# MCU.net
KiCad netlist of a schematic drawn in Altium Designer
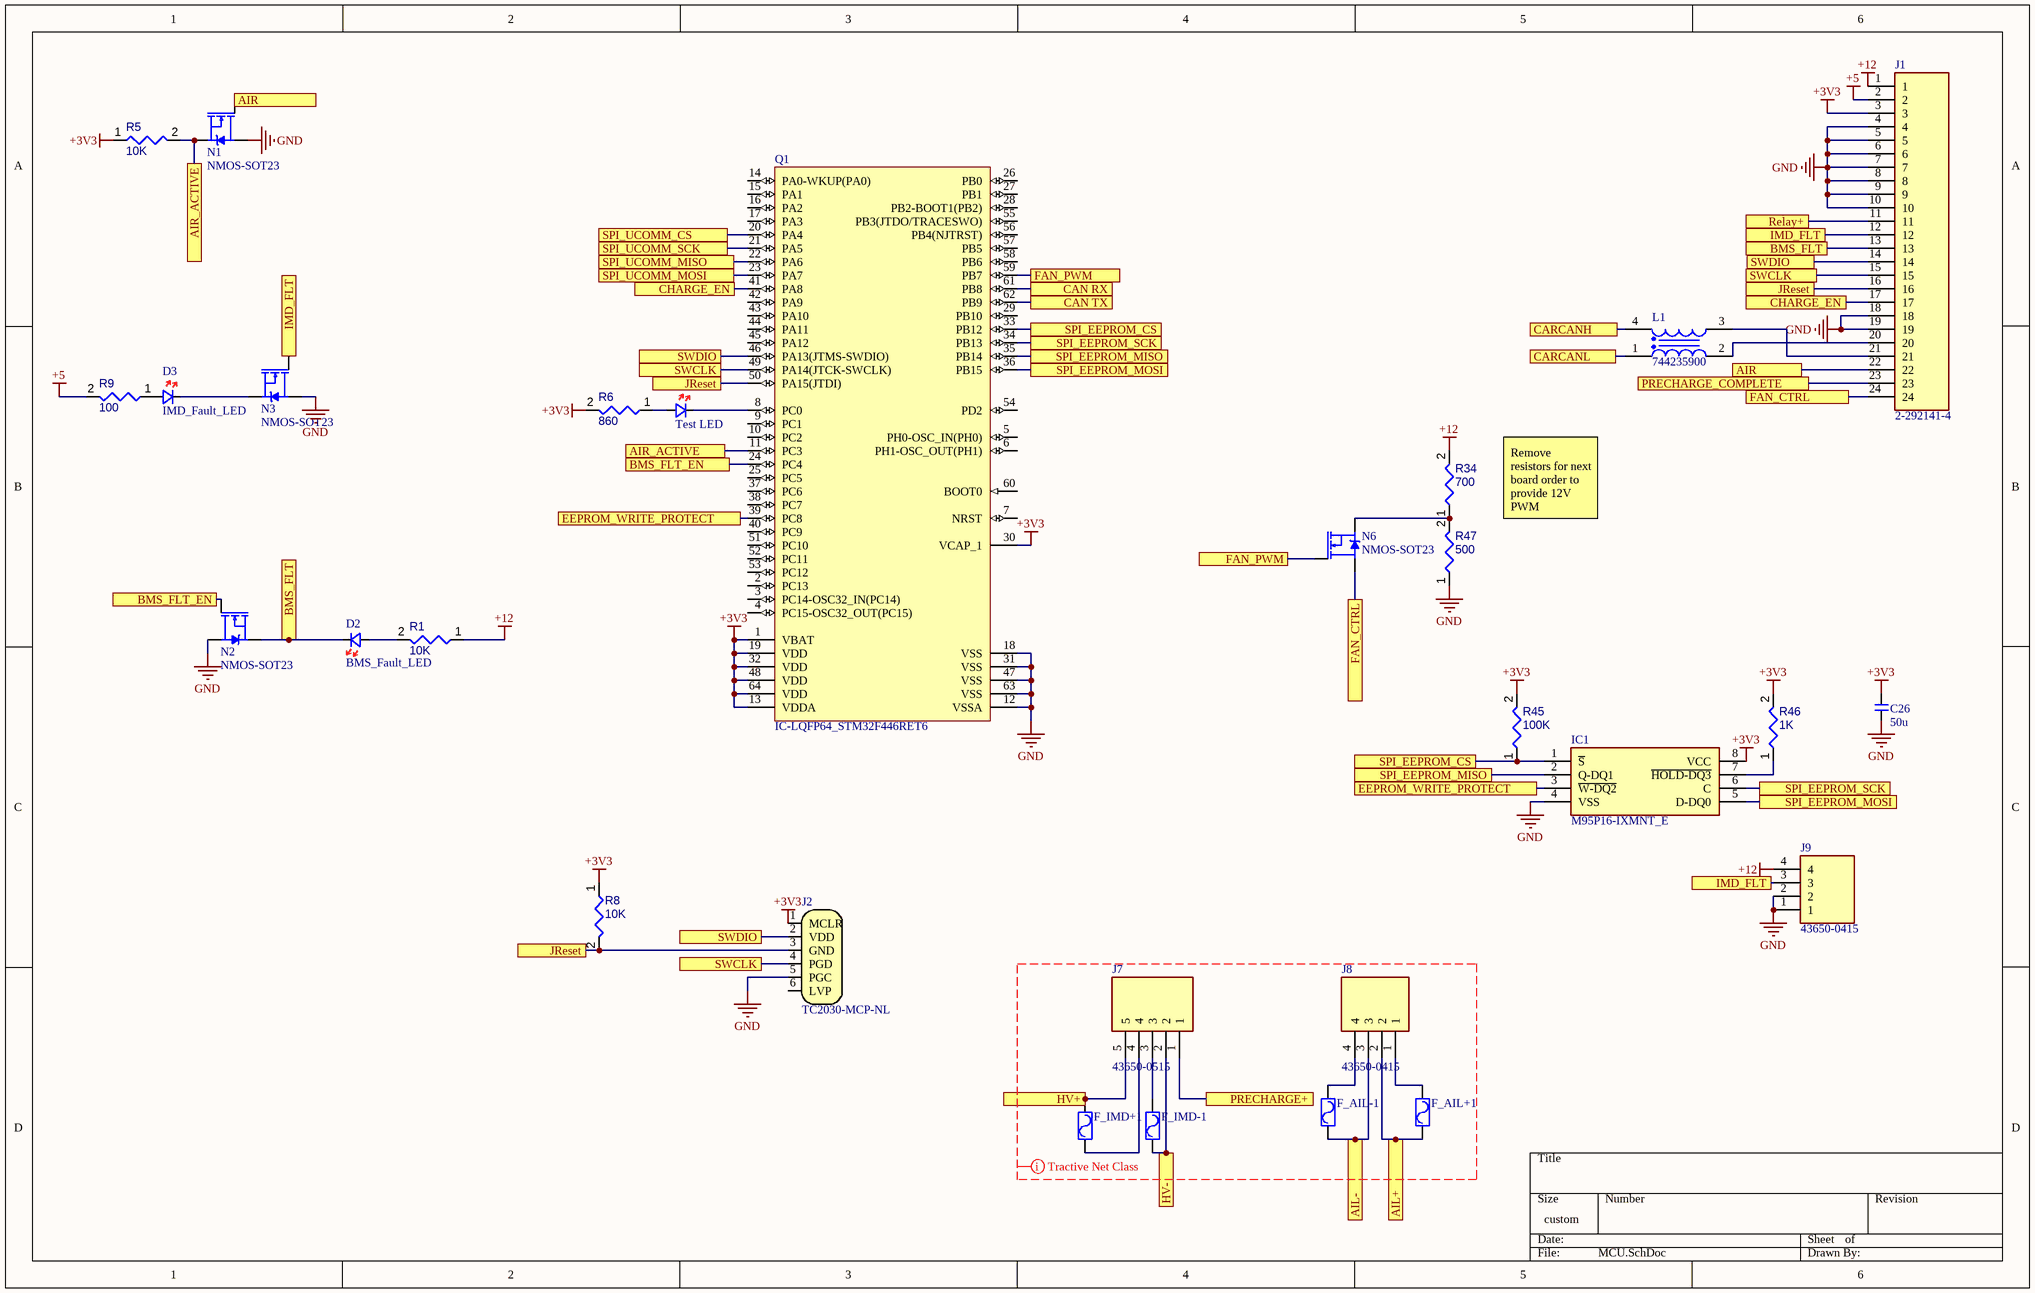
[diagram p0: MCU.SchDoc]

(export (version "E")
  (design (tool "Eeschema 10.0.6"))
  (components
    (comp (ref "C26")
      (value "50u")
      (footprint "CAP-0603")
      (fields (field (name "SOURCE") "ife19_Elec_Library.SchLib"))
      (libsource (lib "Illini Formula Electric") (part "CAP-0603"))
    )
    (comp (ref "D1")
      (value "Test LED")
      (footprint "LEDRED-0603")
      (fields (field (name "SOURCE") "ife19_Elec_Library.SchLib"))
      (libsource (lib "Illini Formula Electric") (part "LED_XZFBB45S"))
    )
    (comp (ref "D2")
      (value "BMS_Fault_LED")
      (footprint "LEDRED-0603")
      (fields (field (name "SOURCE") "ife19_Elec_Library.SchLib"))
      (libsource (lib "Illini Formula Electric") (part "LED_XZFBB45S"))
    )
    (comp (ref "D3")
      (value "IMD_Fault_LED")
      (footprint "LEDRED-0603")
      (fields (field (name "SOURCE") "ife19_Elec_Library.SchLib"))
      (libsource (lib "Illini Formula Electric") (part "LED_XZFBB45S"))
    )
    (comp (ref "F_AIL+1")
      (value "~")
      (footprint "FUSE_885")
      (fields (field (name "SOURCE") "ife19_Elec_Library.SchLib"))
      (libsource (lib "Illini Formula Electric") (part "FUSE-354101"))
    )
    (comp (ref "F_AIL-1")
      (value "~")
      (footprint "FUSE_885")
      (fields (field (name "SOURCE") "ife19_Elec_Library.SchLib"))
      (libsource (lib "Illini Formula Electric") (part "FUSE-354101"))
    )
    (comp (ref "F_IMD+1")
      (value "~")
      (footprint "FUSE_885")
      (fields (field (name "SOURCE") "ife19_Elec_Library.SchLib"))
      (libsource (lib "Illini Formula Electric") (part "FUSE-354101"))
    )
    (comp (ref "F_IMD-1")
      (value "~")
      (footprint "FUSE_885")
      (fields (field (name "SOURCE") "ife19_Elec_Library.SchLib"))
      (libsource (lib "Illini Formula Electric") (part "FUSE-354101"))
    )
    (comp (ref "IC1")
      (value "M95P16-IXMNT_E")
      (footprint "SamacSys:SOIC127P600X175-8N")
      (description "Integrated Circuit")
      (fields (field (name "MANUFACTURER_PART_NUMBER") "M95P16-IXMNT/E"))
      (libsource (lib "*") (part "M95P16-IXMNT_E"))
    )
    (comp (ref "J1")
      (value "2-292141-4")
      (footprint "TE_2-292141-4")
      (description "CT DOUBLE ROW ASSY V 24P W/BOS")
      (fields (field (name "MF") "TE Connectivity"))
      (libsource (lib "Illini Formula Electric") (part "2-292141-4"))
    )
    (comp (ref "J2")
      (value "TC2030-MCP-NL")
      (footprint "TC2030-MCP-NL")
      (description "Conector par ICD")
      (fields (field (name "SOURCE") "Image Pasted at 2021-10-31 17-08.SchLib"))
      (libsource (lib "Illini Formula Electric") (part "TC2030-MCP-NL"))
    )
    (comp (ref "J7")
      (value "43650-0515")
      (footprint "SamacSys:43650-05YY_151617")
      (description "Connector")
      (fields (field (name "MOUSER PART NUMBER") "538-43650-0515"))
      (libsource (lib "*") (part "43650-0515"))
    )
    (comp (ref "J8")
      (value "43650-0415")
      (footprint "SamacSys:43650-04YY_151617")
      (description "Connector")
      (fields (field (name "MOUSER PART NUMBER") "538-43650-0415"))
      (libsource (lib "*") (part "43650-0415"))
    )
    (comp (ref "J9")
      (value "43650-0415")
      (footprint "SamacSys:43650-04YY_151617")
      (description "Connector")
      (fields (field (name "MOUSER PART NUMBER") "538-43650-0415"))
      (libsource (lib "") (part "43650-0415_1"))
    )
    (comp (ref "L1")
      (value "744235900")
      (footprint "WE-CNSW_1812")
      (fields (field (name "TOLERANCE") "25%"))
      (libsource (lib "Altium Content Vault") (part "WE-CNSW"))
    )
    (comp (ref "N1")
      (value "NMOS-SOT23")
      (footprint "SOT23")
      (fields (field (name "SOURCE") "ife19_Elec_Library.SchLib"))
      (libsource (lib "Illini Formula Electric") (part "NMOS-SOT23"))
    )
    (comp (ref "N2")
      (value "NMOS-SOT23")
      (footprint "SOT23")
      (fields (field (name "SOURCE") "ife19_Elec_Library.SchLib"))
      (libsource (lib "Illini Formula Electric") (part "NMOS-SOT23"))
    )
    (comp (ref "N3")
      (value "NMOS-SOT23")
      (footprint "SOT23")
      (fields (field (name "SOURCE") "ife19_Elec_Library.SchLib"))
      (libsource (lib "Illini Formula Electric") (part "NMOS-SOT23"))
    )
    (comp (ref "N6")
      (value "NMOS-SOT23")
      (footprint "SOT23")
      (fields (field (name "SOURCE") "ife19_Elec_Library.SchLib"))
      (libsource (lib "Illini Formula Electric") (part "NMOS-SOT23"))
    )
    (comp (ref "Q1")
      (value "IC-LQFP64_STM32F446RET6")
      (footprint "TSQFP50P1200X1200X160-64N")
      (description "IC MCU 32BIT 512KB FLASH 64LQFP")
      (fields
        (field (name "MANUFACTURER PART NUMBER") "STM32F446RET6")
        (field (name "MANUFACTURER") "STMicroelectronics")
        (field (name "SOURCE") "ife19_Elec_Library.SchLib")
      )
      (libsource (lib "Illini Formula Electric") (part "IC-LQFP64_STM32F446RET6"))
    )
    (comp (ref "R1")
      (value "10K")
      (footprint "RESC0805(2012)_L")
      (description "Chip Resistor, 43,2 kOhms, +/-1 %, 63 mW, -55 to 155 degC, 0402")
      (fields (field (name "AVAILABLE PREVIEW IMAGES") "2D"))
      (libsource (lib "Illini Formula Electric") (part "Symbol"))
    )
    (comp (ref "R5")
      (value "10K")
      (footprint "RESC0805(2012)_L")
      (description "Chip Resistor, 43,2 kOhms, +/-1 %, 63 mW, -55 to 155 degC, 0402")
      (fields (field (name "AVAILABLE PREVIEW IMAGES") "2D"))
      (libsource (lib "Illini Formula Electric") (part "Symbol"))
    )
    (comp (ref "R6")
      (value "860")
      (footprint "RESC0805(2012)_L")
      (description "Chip Resistor, 43,2 kOhms, +/-1 %, 63 mW, -55 to 155 degC, 0402")
      (fields (field (name "AVAILABLE PREVIEW IMAGES") "2D"))
      (libsource (lib "Illini Formula Electric") (part "Symbol"))
    )
    (comp (ref "R8")
      (value "10K")
      (footprint "RESC0805(2012)_L")
      (description "Chip Resistor, 43,2 kOhms, +/-1 %, 63 mW, -55 to 155 degC, 0402")
      (fields (field (name "AVAILABLE PREVIEW IMAGES") "2D"))
      (libsource (lib "Illini Formula Electric") (part "Symbol"))
    )
    (comp (ref "R9")
      (value "100")
      (footprint "RESC0805(2012)_L")
      (description "Chip Resistor, 43,2 kOhms, +/-1 %, 63 mW, -55 to 155 degC, 0402")
      (fields (field (name "AVAILABLE PREVIEW IMAGES") "2D"))
      (libsource (lib "Illini Formula Electric") (part "Symbol"))
    )
    (comp (ref "R34")
      (value "700")
      (footprint "RESC0805(2012)_L")
      (description "Chip Resistor, 43,2 kOhms, +/-1 %, 63 mW, -55 to 155 degC, 0402")
      (fields (field (name "AVAILABLE PREVIEW IMAGES") "2D"))
      (libsource (lib "Illini Formula Electric") (part "Symbol"))
    )
    (comp (ref "R45")
      (value "100K")
      (footprint "RESC0805(2012)_L")
      (description "Chip Resistor, 43,2 kOhms, +/-1 %, 63 mW, -55 to 155 degC, 0402")
      (fields (field (name "AVAILABLE PREVIEW IMAGES") "2D"))
      (libsource (lib "Illini Formula Electric") (part "Symbol"))
    )
    (comp (ref "R46")
      (value "1K")
      (footprint "RESC0805(2012)_L")
      (description "Chip Resistor, 43,2 kOhms, +/-1 %, 63 mW, -55 to 155 degC, 0402")
      (fields (field (name "AVAILABLE PREVIEW IMAGES") "2D"))
      (libsource (lib "Illini Formula Electric") (part "Symbol"))
    )
    (comp (ref "R47")
      (value "500")
      (footprint "RESC0805(2012)_L")
      (description "Chip Resistor, 43,2 kOhms, +/-1 %, 63 mW, -55 to 155 degC, 0402")
      (fields (field (name "AVAILABLE PREVIEW IMAGES") "2D"))
      (libsource (lib "Illini Formula Electric") (part "Symbol"))
    )
  )
  (nets
    (net (code "1") (name "+3V3") (class "Default")
      (node (ref "C26") (pin "1") (pinfunction "1_1") (pintype "passive"))
      (node (ref "IC1") (pin "8") (pinfunction "VCC_8") (pintype "passive"))
      (node (ref "J1") (pin "3") (pinfunction "3_3") (pintype "passive"))
      (node (ref "J2") (pin "1") (pinfunction "MCLR_1") (pintype "passive"))
      (node (ref "Q1") (pin "1") (pinfunction "VBAT_1") (pintype "power_in"))
      (node (ref "Q1") (pin "13") (pinfunction "VDDA_13") (pintype "power_in"))
      (node (ref "Q1") (pin "19") (pinfunction "VDD_19") (pintype "power_in"))
      (node (ref "Q1") (pin "30") (pinfunction "VCAP_1_30") (pintype "passive"))
      (node (ref "Q1") (pin "32") (pinfunction "VDD_32") (pintype "power_in"))
      (node (ref "Q1") (pin "48") (pinfunction "VDD_48") (pintype "power_in"))
      (node (ref "Q1") (pin "64") (pinfunction "VDD_64") (pintype "power_in"))
      (node (ref "R45") (pin "2") (pinfunction "2_2") (pintype "passive"))
      (node (ref "R46") (pin "2") (pinfunction "2_2") (pintype "passive"))
      (node (ref "R5") (pin "1") (pinfunction "1_1") (pintype "passive"))
      (node (ref "R6") (pin "2") (pinfunction "2_2") (pintype "passive"))
      (node (ref "R8") (pin "1") (pinfunction "1_1") (pintype "passive"))
    )
    (net (code "2") (name "+5") (class "Default")
      (node (ref "J1") (pin "2") (pinfunction "2_2") (pintype "passive"))
      (node (ref "R9") (pin "2") (pinfunction "2_2") (pintype "passive"))
    )
    (net (code "3") (name "+12") (class "Default")
      (node (ref "J1") (pin "1") (pinfunction "1_1") (pintype "passive"))
      (node (ref "J9") (pin "4") (pinfunction "4_4") (pintype "passive"))
      (node (ref "R1") (pin "1") (pinfunction "1_1") (pintype "passive"))
      (node (ref "R34") (pin "2") (pinfunction "2_2") (pintype "passive"))
    )
    (net (code "4") (name "/AIL+") (class "Default")
      (node (ref "F_AIL+1") (pin "2") (pinfunction "2_2") (pintype "passive"))
      (node (ref "J8") (pin "2") (pinfunction "2_2") (pintype "passive"))
    )
    (net (code "5") (name "/AIL-") (class "Default")
      (node (ref "F_AIL-1") (pin "2") (pinfunction "2_2") (pintype "passive"))
      (node (ref "J8") (pin "3") (pinfunction "3_3") (pintype "passive"))
    )
    (net (code "6") (name "/AIR") (class "Default")
      (node (ref "J1") (pin "22") (pinfunction "22_22") (pintype "passive"))
      (node (ref "N1") (pin "1") (pinfunction "G_1") (pintype "passive"))
    )
    (net (code "7") (name "/AIR_ACTIVE") (class "Default")
      (node (ref "N1") (pin "3") (pinfunction "D_3") (pintype "passive"))
      (node (ref "Q1") (pin "11") (pinfunction "PC3_11") (pintype "bidirectional"))
      (node (ref "R5") (pin "2") (pinfunction "2_2") (pintype "passive"))
    )
    (net (code "8") (name "/BMS_FLT") (class "Default")
      (node (ref "D2") (pin "K") (pinfunction "K_K") (pintype "passive"))
      (node (ref "J1") (pin "13") (pinfunction "13_13") (pintype "passive"))
      (node (ref "N2") (pin "3") (pinfunction "D_3") (pintype "passive"))
    )
    (net (code "9") (name "/BMS_FLT_EN") (class "Default")
      (node (ref "N2") (pin "1") (pinfunction "G_1") (pintype "passive"))
      (node (ref "Q1") (pin "24") (pinfunction "PC4_24") (pintype "bidirectional"))
    )
    (net (code "10") (name "/CAN RX") (class "Default")
      (node (ref "Q1") (pin "61") (pinfunction "PB8_61") (pintype "bidirectional"))
    )
    (net (code "11") (name "/CAN TX") (class "Default")
      (node (ref "Q1") (pin "62") (pinfunction "PB9_62") (pintype "bidirectional"))
    )
    (net (code "12") (name "/CARCANH") (class "Default")
      (node (ref "L1") (pin "4") (pinfunction "4_4") (pintype "passive"))
    )
    (net (code "13") (name "/CARCANL") (class "Default")
      (node (ref "L1") (pin "1") (pinfunction "1_1") (pintype "passive"))
    )
    (net (code "14") (name "/CHARGE_EN") (class "Default")
      (node (ref "J1") (pin "17") (pinfunction "17_17") (pintype "passive"))
      (node (ref "Q1") (pin "41") (pinfunction "PA8_41") (pintype "bidirectional"))
    )
    (net (code "15") (name "/EEPROM_WRITE_PROTECT") (class "Default")
      (node (ref "IC1") (pin "3") (pinfunction "~{W-DQ2}_3") (pintype "passive"))
      (node (ref "Q1") (pin "39") (pinfunction "PC8_39") (pintype "bidirectional"))
    )
    (net (code "16") (name "/FAN_CTRL") (class "Default")
      (node (ref "J1") (pin "24") (pinfunction "24_24") (pintype "passive"))
      (node (ref "N6") (pin "2") (pinfunction "S_2") (pintype "passive"))
    )
    (net (code "17") (name "/FAN_PWM") (class "Default")
      (node (ref "N6") (pin "1") (pinfunction "G_1") (pintype "passive"))
      (node (ref "Q1") (pin "59") (pinfunction "PB7_59") (pintype "bidirectional"))
    )
    (net (code "18") (name "/HV+") (class "Default")
      (node (ref "F_IMD+1") (pin "1") (pinfunction "1_1") (pintype "passive"))
      (node (ref "J7") (pin "5") (pinfunction "5_5") (pintype "passive"))
    )
    (net (code "19") (name "/HV-") (class "Default")
      (node (ref "F_IMD-1") (pin "2") (pinfunction "2_2") (pintype "passive"))
      (node (ref "J7") (pin "2") (pinfunction "2_2") (pintype "passive"))
    )
    (net (code "20") (name "/IMD_FLT") (class "Default")
      (node (ref "J1") (pin "12") (pinfunction "12_12") (pintype "passive"))
      (node (ref "J9") (pin "3") (pinfunction "3_3") (pintype "passive"))
      (node (ref "N3") (pin "1") (pinfunction "G_1") (pintype "passive"))
    )
    (net (code "21") (name "/JReset") (class "Default")
      (node (ref "J1") (pin "16") (pinfunction "16_16") (pintype "passive"))
      (node (ref "J2") (pin "3") (pinfunction "GND_3") (pintype "passive"))
      (node (ref "Q1") (pin "50") (pinfunction "PA15(JTDI)_50") (pintype "bidirectional"))
      (node (ref "R8") (pin "2") (pinfunction "2_2") (pintype "passive"))
    )
    (net (code "22") (name "/PRECHARGE+") (class "Default")
      (node (ref "J7") (pin "1") (pinfunction "1_1") (pintype "passive"))
    )
    (net (code "23") (name "/PRECHARGE_COMPLETE") (class "Default")
      (node (ref "J1") (pin "23") (pinfunction "23_23") (pintype "passive"))
    )
    (net (code "24") (name "/Relay+") (class "Default")
      (node (ref "J1") (pin "11") (pinfunction "11_11") (pintype "passive"))
    )
    (net (code "25") (name "/SPI_EEPROM_CS") (class "Default")
      (node (ref "IC1") (pin "1") (pinfunction "~{S}_1") (pintype "passive"))
      (node (ref "Q1") (pin "33") (pinfunction "PB12_33") (pintype "bidirectional"))
      (node (ref "R45") (pin "1") (pinfunction "1_1") (pintype "passive"))
    )
    (net (code "26") (name "/SPI_EEPROM_MISO") (class "Default")
      (node (ref "IC1") (pin "2") (pinfunction "Q-DQ1_2") (pintype "passive"))
      (node (ref "Q1") (pin "35") (pinfunction "PB14_35") (pintype "bidirectional"))
    )
    (net (code "27") (name "/SPI_EEPROM_MOSI") (class "Default")
      (node (ref "IC1") (pin "5") (pinfunction "D-DQ0_5") (pintype "passive"))
      (node (ref "Q1") (pin "36") (pinfunction "PB15_36") (pintype "bidirectional"))
    )
    (net (code "28") (name "/SPI_EEPROM_SCK") (class "Default")
      (node (ref "IC1") (pin "6") (pinfunction "C_6") (pintype "passive"))
      (node (ref "Q1") (pin "34") (pinfunction "PB13_34") (pintype "bidirectional"))
    )
    (net (code "29") (name "/SPI_UCOMM_CS") (class "Default")
      (node (ref "Q1") (pin "20") (pinfunction "PA4_20") (pintype "bidirectional"))
    )
    (net (code "30") (name "/SPI_UCOMM_MISO") (class "Default")
      (node (ref "Q1") (pin "22") (pinfunction "PA6_22") (pintype "bidirectional"))
    )
    (net (code "31") (name "/SPI_UCOMM_MOSI") (class "Default")
      (node (ref "Q1") (pin "23") (pinfunction "PA7_23") (pintype "bidirectional"))
    )
    (net (code "32") (name "/SPI_UCOMM_SCK") (class "Default")
      (node (ref "Q1") (pin "21") (pinfunction "PA5_21") (pintype "bidirectional"))
    )
    (net (code "33") (name "/SWCLK") (class "Default")
      (node (ref "J1") (pin "15") (pinfunction "15_15") (pintype "passive"))
      (node (ref "J2") (pin "4") (pinfunction "PGD_4") (pintype "passive"))
      (node (ref "Q1") (pin "49") (pinfunction "PA14(JTCK-SWCLK)_49") (pintype "bidirectional"))
    )
    (net (code "34") (name "/SWDIO") (class "Default")
      (node (ref "J1") (pin "14") (pinfunction "14_14") (pintype "passive"))
      (node (ref "J2") (pin "2") (pinfunction "VDD_2") (pintype "passive"))
      (node (ref "Q1") (pin "46") (pinfunction "PA13(JTMS-SWDIO)_46") (pintype "bidirectional"))
    )
    (net (code "35") (name "GND") (class "Default")
      (node (ref "C26") (pin "2") (pinfunction "2_2") (pintype "passive"))
      (node (ref "IC1") (pin "4") (pinfunction "VSS_4") (pintype "passive"))
      (node (ref "J1") (pin "10") (pinfunction "10_10") (pintype "passive"))
      (node (ref "J1") (pin "18") (pinfunction "18_18") (pintype "passive"))
      (node (ref "J1") (pin "19") (pinfunction "19_19") (pintype "passive"))
      (node (ref "J1") (pin "4") (pinfunction "4_4") (pintype "passive"))
      (node (ref "J1") (pin "5") (pinfunction "5_5") (pintype "passive"))
      (node (ref "J1") (pin "6") (pinfunction "6_6") (pintype "passive"))
      (node (ref "J1") (pin "7") (pinfunction "7_7") (pintype "passive"))
      (node (ref "J1") (pin "8") (pinfunction "8_8") (pintype "passive"))
      (node (ref "J1") (pin "9") (pinfunction "9_9") (pintype "passive"))
      (node (ref "J2") (pin "5") (pinfunction "PGC_5") (pintype "passive"))
      (node (ref "J9") (pin "1") (pinfunction "1_1") (pintype "passive"))
      (node (ref "J9") (pin "2") (pinfunction "2_2") (pintype "passive"))
      (node (ref "N1") (pin "2") (pinfunction "S_2") (pintype "passive"))
      (node (ref "N2") (pin "2") (pinfunction "S_2") (pintype "passive"))
      (node (ref "N3") (pin "2") (pinfunction "S_2") (pintype "passive"))
      (node (ref "Q1") (pin "12") (pinfunction "VSSA_12") (pintype "power_in"))
      (node (ref "Q1") (pin "18") (pinfunction "VSS_18") (pintype "power_in"))
      (node (ref "Q1") (pin "31") (pinfunction "VSS_31") (pintype "power_in"))
      (node (ref "Q1") (pin "47") (pinfunction "VSS_47") (pintype "power_in"))
      (node (ref "Q1") (pin "63") (pinfunction "VSS_63") (pintype "power_in"))
      (node (ref "R47") (pin "1") (pinfunction "1_1") (pintype "passive"))
    )
    (net (code "36") (name "Net-(D1-PadA)") (class "Default")
      (node (ref "D1") (pin "A") (pinfunction "A_A") (pintype "passive"))
      (node (ref "R6") (pin "1") (pinfunction "1_1") (pintype "passive"))
    )
    (net (code "37") (name "Net-(D2-PadA)") (class "Default")
      (node (ref "D2") (pin "A") (pinfunction "A_A") (pintype "passive"))
      (node (ref "R1") (pin "2") (pinfunction "2_2") (pintype "passive"))
    )
    (net (code "38") (name "Net-(D3-PadA)") (class "Default")
      (node (ref "D3") (pin "A") (pinfunction "A_A") (pintype "passive"))
      (node (ref "R9") (pin "1") (pinfunction "1_1") (pintype "passive"))
    )
    (net (code "39") (name "Net-(F_AIL+1-Pad1)") (class "Default")
      (node (ref "F_AIL+1") (pin "1") (pinfunction "1_1") (pintype "passive"))
      (node (ref "J8") (pin "1") (pinfunction "1_1") (pintype "passive"))
    )
    (net (code "40") (name "Net-(F_AIL-1-Pad1)") (class "Default")
      (node (ref "F_AIL-1") (pin "1") (pinfunction "1_1") (pintype "passive"))
      (node (ref "J8") (pin "4") (pinfunction "4_4") (pintype "passive"))
    )
    (net (code "41") (name "Net-(F_IMD+1-Pad2)") (class "Default")
      (node (ref "F_IMD+1") (pin "2") (pinfunction "2_2") (pintype "passive"))
      (node (ref "J7") (pin "4") (pinfunction "4_4") (pintype "passive"))
    )
    (net (code "42") (name "Net-(F_IMD-1-Pad1)") (class "Default")
      (node (ref "F_IMD-1") (pin "1") (pinfunction "1_1") (pintype "passive"))
      (node (ref "J7") (pin "3") (pinfunction "3_3") (pintype "passive"))
    )
    (net (code "43") (name "Net-(IC1-~{HOLD-DQ3})") (class "Default")
      (node (ref "IC1") (pin "7") (pinfunction "~{HOLD-DQ3}_7") (pintype "passive"))
      (node (ref "R46") (pin "1") (pinfunction "1_1") (pintype "passive"))
    )
    (net (code "44") (name "Net-(J1-Pad20)") (class "Default")
      (node (ref "J1") (pin "20") (pinfunction "20_20") (pintype "passive"))
      (node (ref "L1") (pin "2") (pinfunction "2_2") (pintype "passive"))
    )
    (net (code "45") (name "Net-(J1-Pad21)") (class "Default")
      (node (ref "J1") (pin "21") (pinfunction "21_21") (pintype "passive"))
      (node (ref "L1") (pin "3") (pinfunction "3_3") (pintype "passive"))
    )
    (net (code "46") (name "Net-(N3-D)") (class "Default")
      (node (ref "D3") (pin "K") (pinfunction "K_K") (pintype "passive"))
      (node (ref "N3") (pin "3") (pinfunction "D_3") (pintype "passive"))
    )
    (net (code "47") (name "Net-(N6-D)") (class "Default")
      (node (ref "N6") (pin "3") (pinfunction "D_3") (pintype "passive"))
      (node (ref "R34") (pin "1") (pinfunction "1_1") (pintype "passive"))
      (node (ref "R47") (pin "2") (pinfunction "2_2") (pintype "passive"))
    )
    (net (code "48") (name "Net-(Q1-PC0)") (class "Default")
      (node (ref "D1") (pin "K") (pinfunction "K_K") (pintype "passive"))
      (node (ref "Q1") (pin "8") (pinfunction "PC0_8") (pintype "bidirectional"))
    )
    (net (code "49") (name "unconnected-(J2-LVP-Pad6)") (class "Default")
      (node (ref "J2") (pin "6") (pinfunction "LVP_6") (pintype "passive"))
    )
    (net (code "50") (name "unconnected-(Q1-BOOT0-Pad60)") (class "Default")
      (node (ref "Q1") (pin "60") (pinfunction "BOOT0_60") (pintype "input"))
    )
    (net (code "51") (name "unconnected-(Q1-NRST-Pad7)") (class "Default")
      (node (ref "Q1") (pin "7") (pinfunction "NRST_7") (pintype "bidirectional"))
    )
    (net (code "52") (name "unconnected-(Q1-PA0-WKUP(PA0)-Pad14)") (class "Default")
      (node (ref "Q1") (pin "14") (pinfunction "PA0-WKUP(PA0)_14") (pintype "bidirectional"))
    )
    (net (code "53") (name "unconnected-(Q1-PA1-Pad15)") (class "Default")
      (node (ref "Q1") (pin "15") (pinfunction "PA1_15") (pintype "bidirectional"))
    )
    (net (code "54") (name "unconnected-(Q1-PA2-Pad16)") (class "Default")
      (node (ref "Q1") (pin "16") (pinfunction "PA2_16") (pintype "bidirectional"))
    )
    (net (code "55") (name "unconnected-(Q1-PA3-Pad17)") (class "Default")
      (node (ref "Q1") (pin "17") (pinfunction "PA3_17") (pintype "bidirectional"))
    )
    (net (code "56") (name "unconnected-(Q1-PA9-Pad42)") (class "Default")
      (node (ref "Q1") (pin "42") (pinfunction "PA9_42") (pintype "bidirectional"))
    )
    (net (code "57") (name "unconnected-(Q1-PA10-Pad43)") (class "Default")
      (node (ref "Q1") (pin "43") (pinfunction "PA10_43") (pintype "bidirectional"))
    )
    (net (code "58") (name "unconnected-(Q1-PA11-Pad44)") (class "Default")
      (node (ref "Q1") (pin "44") (pinfunction "PA11_44") (pintype "bidirectional"))
    )
    (net (code "59") (name "unconnected-(Q1-PA12-Pad45)") (class "Default")
      (node (ref "Q1") (pin "45") (pinfunction "PA12_45") (pintype "bidirectional"))
    )
    (net (code "60") (name "unconnected-(Q1-PB0-Pad26)") (class "Default")
      (node (ref "Q1") (pin "26") (pinfunction "PB0_26") (pintype "bidirectional"))
    )
    (net (code "61") (name "unconnected-(Q1-PB1-Pad27)") (class "Default")
      (node (ref "Q1") (pin "27") (pinfunction "PB1_27") (pintype "bidirectional"))
    )
    (net (code "62") (name "unconnected-(Q1-PB2-BOOT1(PB2)-Pad28)") (class "Default")
      (node (ref "Q1") (pin "28") (pinfunction "PB2-BOOT1(PB2)_28") (pintype "bidirectional"))
    )
    (net (code "63") (name "unconnected-(Q1-PB3(JTDO{slash}TRACESWO)-Pad55)") (class "Default")
      (node (ref "Q1") (pin "55") (pinfunction "PB3(JTDO/TRACESWO)_55") (pintype "bidirectional"))
    )
    (net (code "64") (name "unconnected-(Q1-PB4(NJTRST)-Pad56)") (class "Default")
      (node (ref "Q1") (pin "56") (pinfunction "PB4(NJTRST)_56") (pintype "bidirectional"))
    )
    (net (code "65") (name "unconnected-(Q1-PB5-Pad57)") (class "Default")
      (node (ref "Q1") (pin "57") (pinfunction "PB5_57") (pintype "bidirectional"))
    )
    (net (code "66") (name "unconnected-(Q1-PB6-Pad58)") (class "Default")
      (node (ref "Q1") (pin "58") (pinfunction "PB6_58") (pintype "bidirectional"))
    )
    (net (code "67") (name "unconnected-(Q1-PB10-Pad29)") (class "Default")
      (node (ref "Q1") (pin "29") (pinfunction "PB10_29") (pintype "bidirectional"))
    )
    (net (code "68") (name "unconnected-(Q1-PC1-Pad9)") (class "Default")
      (node (ref "Q1") (pin "9") (pinfunction "PC1_9") (pintype "bidirectional"))
    )
    (net (code "69") (name "unconnected-(Q1-PC2-Pad10)") (class "Default")
      (node (ref "Q1") (pin "10") (pinfunction "PC2_10") (pintype "bidirectional"))
    )
    (net (code "70") (name "unconnected-(Q1-PC5-Pad25)") (class "Default")
      (node (ref "Q1") (pin "25") (pinfunction "PC5_25") (pintype "bidirectional"))
    )
    (net (code "71") (name "unconnected-(Q1-PC6-Pad37)") (class "Default")
      (node (ref "Q1") (pin "37") (pinfunction "PC6_37") (pintype "bidirectional"))
    )
    (net (code "72") (name "unconnected-(Q1-PC7-Pad38)") (class "Default")
      (node (ref "Q1") (pin "38") (pinfunction "PC7_38") (pintype "bidirectional"))
    )
    (net (code "73") (name "unconnected-(Q1-PC9-Pad40)") (class "Default")
      (node (ref "Q1") (pin "40") (pinfunction "PC9_40") (pintype "bidirectional"))
    )
    (net (code "74") (name "unconnected-(Q1-PC10-Pad51)") (class "Default")
      (node (ref "Q1") (pin "51") (pinfunction "PC10_51") (pintype "bidirectional"))
    )
    (net (code "75") (name "unconnected-(Q1-PC11-Pad52)") (class "Default")
      (node (ref "Q1") (pin "52") (pinfunction "PC11_52") (pintype "bidirectional"))
    )
    (net (code "76") (name "unconnected-(Q1-PC12-Pad53)") (class "Default")
      (node (ref "Q1") (pin "53") (pinfunction "PC12_53") (pintype "bidirectional"))
    )
    (net (code "77") (name "unconnected-(Q1-PC13-Pad2)") (class "Default")
      (node (ref "Q1") (pin "2") (pinfunction "PC13_2") (pintype "bidirectional"))
    )
    (net (code "78") (name "unconnected-(Q1-PC14-OSC32_IN(PC14)-Pad3)") (class "Default")
      (node (ref "Q1") (pin "3") (pinfunction "PC14-OSC32_IN(PC14)_3") (pintype "bidirectional"))
    )
    (net (code "79") (name "unconnected-(Q1-PC15-OSC32_OUT(PC15)-Pad4)") (class "Default")
      (node (ref "Q1") (pin "4") (pinfunction "PC15-OSC32_OUT(PC15)_4") (pintype "bidirectional"))
    )
    (net (code "80") (name "unconnected-(Q1-PD2-Pad54)") (class "Default")
      (node (ref "Q1") (pin "54") (pinfunction "PD2_54") (pintype "bidirectional"))
    )
    (net (code "81") (name "unconnected-(Q1-PH0-OSC_IN(PH0)-Pad5)") (class "Default")
      (node (ref "Q1") (pin "5") (pinfunction "PH0-OSC_IN(PH0)_5") (pintype "bidirectional"))
    )
    (net (code "82") (name "unconnected-(Q1-PH1-OSC_OUT(PH1)-Pad6)") (class "Default")
      (node (ref "Q1") (pin "6") (pinfunction "PH1-OSC_OUT(PH1)_6") (pintype "bidirectional"))
    )
  )
)
